# main.net
KiCad netlist of a schematic drawn in EAGLE
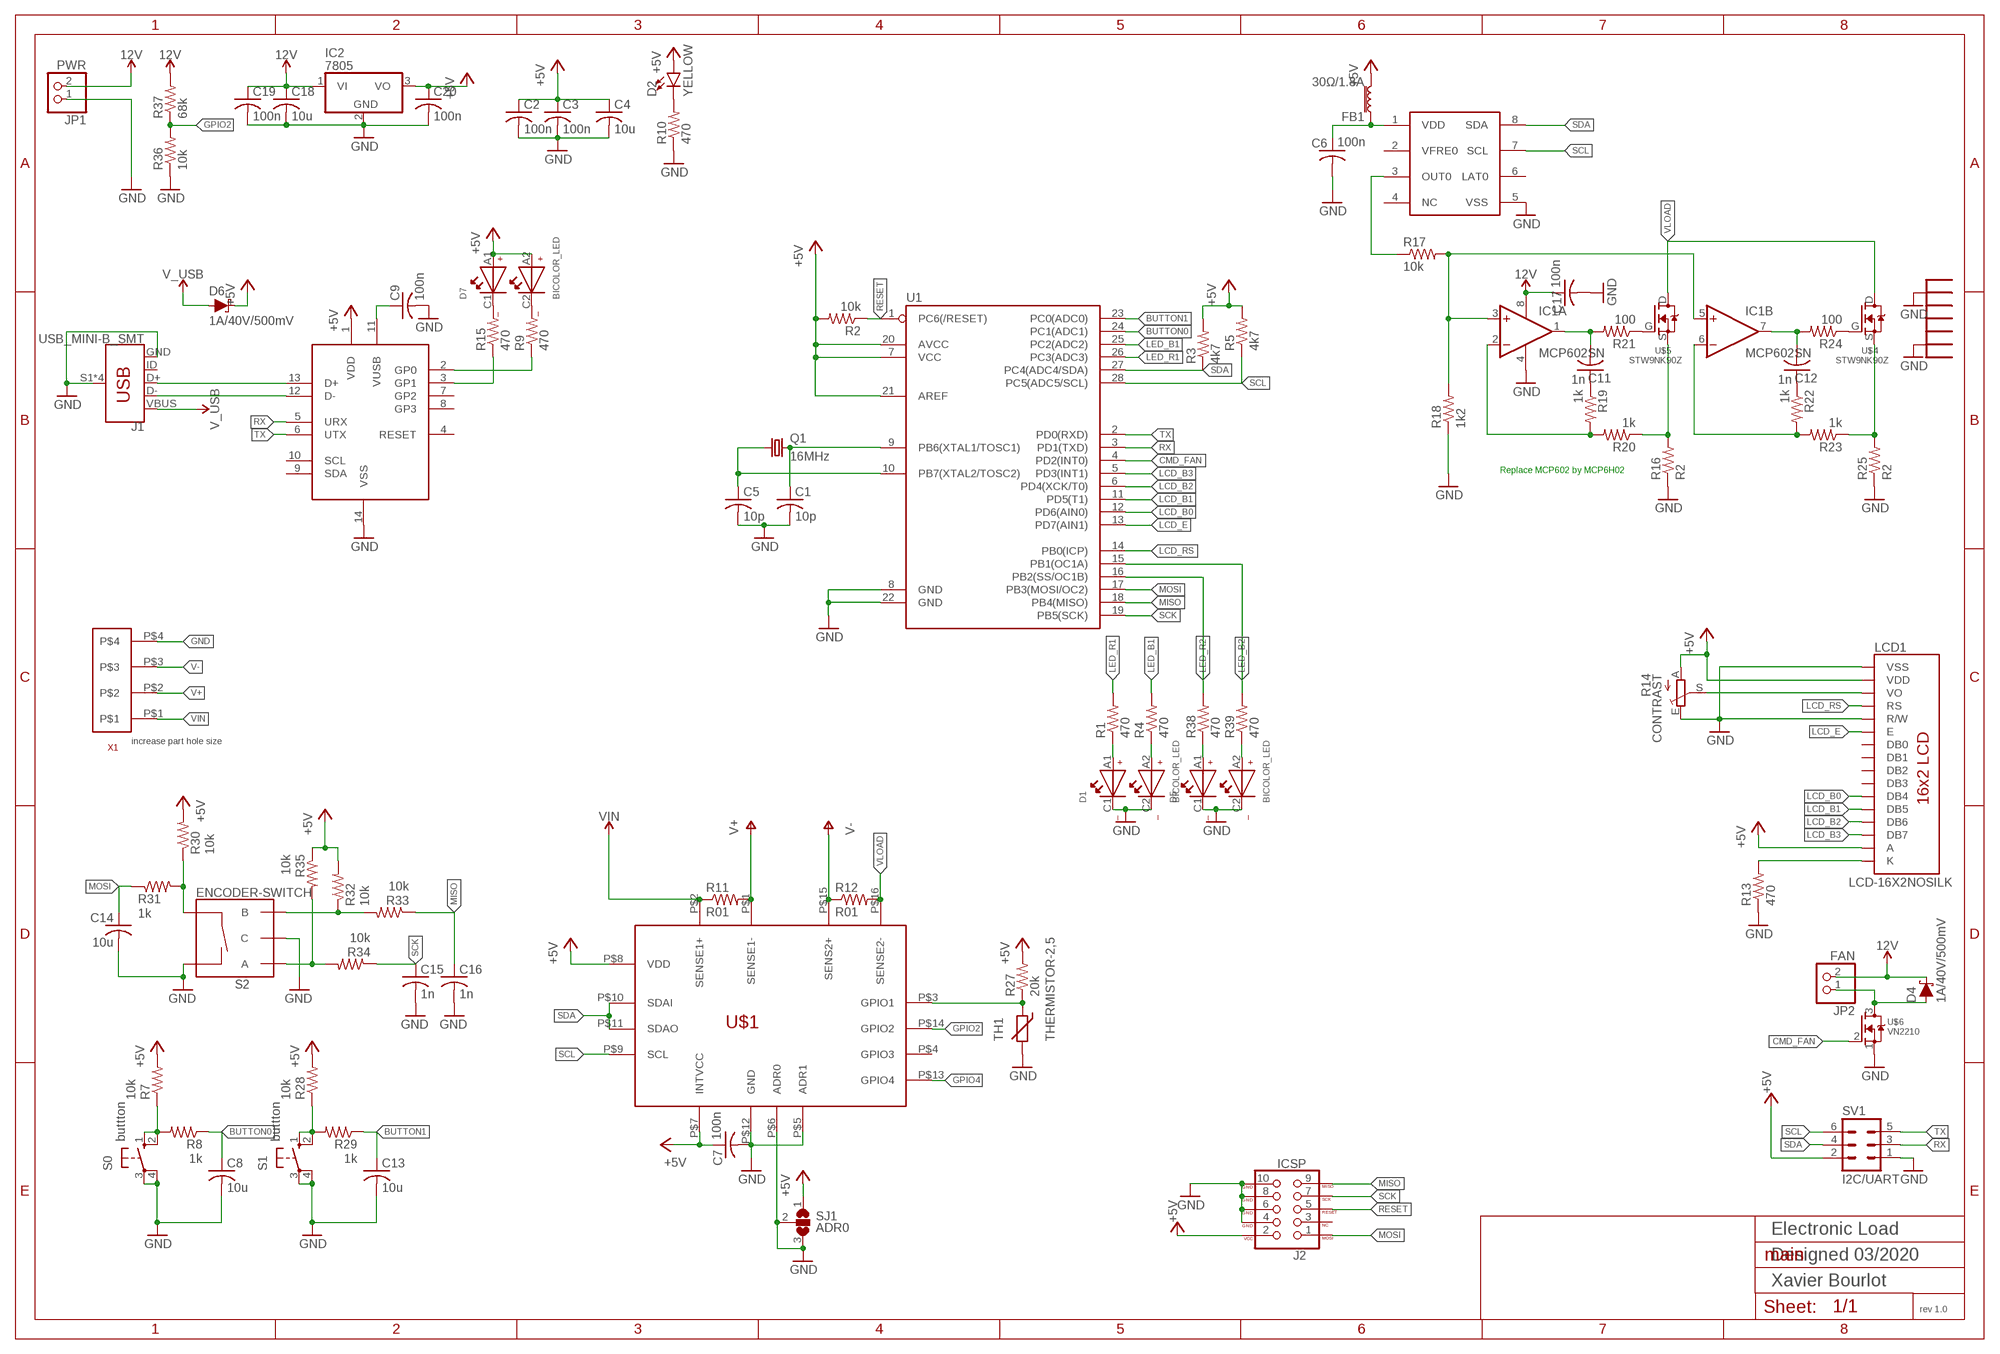
[diagram p0: schematic, sheet 1]

(export (version "E")
  (design (tool "Eeschema 10.0.6"))
  (components
    (comp (ref "BR1")
      (value "MCP2221A")
      (footprint "eagle-import:DIP14")
      (libsource (lib "eagle-import") (part "MCP2221A"))
    )
    (comp (ref "C1")
      (value "10p")
      (footprint "eagle-import:C0603")
      (libsource (lib "eagle-import") (part "C-USC0603"))
    )
    (comp (ref "C2")
      (value "100n")
      (footprint "eagle-import:C0603")
      (libsource (lib "eagle-import") (part "C-USC0603"))
    )
    (comp (ref "C3")
      (value "100n")
      (footprint "eagle-import:C0603")
      (libsource (lib "eagle-import") (part "C-USC0603"))
    )
    (comp (ref "C4")
      (value "10u")
      (footprint "eagle-import:C1206")
      (libsource (lib "eagle-import") (part "C-USC1206"))
    )
    (comp (ref "C5")
      (value "10p")
      (footprint "eagle-import:C0603")
      (libsource (lib "eagle-import") (part "C-USC0603"))
    )
    (comp (ref "C6")
      (value "100n")
      (footprint "eagle-import:C0603")
      (libsource (lib "eagle-import") (part "C-USC0603"))
    )
    (comp (ref "C7")
      (value "100n")
      (footprint "eagle-import:C0603")
      (libsource (lib "eagle-import") (part "C-USC0603"))
    )
    (comp (ref "C8")
      (value "10u")
      (footprint "eagle-import:C0603")
      (libsource (lib "eagle-import") (part "C-USC0603"))
    )
    (comp (ref "C9")
      (value "100n")
      (footprint "eagle-import:C0603")
      (libsource (lib "eagle-import") (part "C-USC0603"))
    )
    (comp (ref "C11")
      (value "1n")
      (footprint "eagle-import:C0805")
      (libsource (lib "eagle-import") (part "C-USC0805"))
    )
    (comp (ref "C12")
      (value "1n")
      (footprint "eagle-import:C0805")
      (libsource (lib "eagle-import") (part "C-USC0805"))
    )
    (comp (ref "C13")
      (value "10u")
      (footprint "eagle-import:C0603")
      (libsource (lib "eagle-import") (part "C-USC0603"))
    )
    (comp (ref "C14")
      (value "10u")
      (footprint "eagle-import:C0603")
      (libsource (lib "eagle-import") (part "C-USC0603"))
    )
    (comp (ref "C15")
      (value "1n")
      (footprint "eagle-import:C0603")
      (libsource (lib "eagle-import") (part "C-USC0603"))
    )
    (comp (ref "C16")
      (value "1n")
      (footprint "eagle-import:C0603")
      (libsource (lib "eagle-import") (part "C-USC0603"))
    )
    (comp (ref "C17")
      (value "100n")
      (footprint "eagle-import:C0603")
      (libsource (lib "eagle-import") (part "C-USC0603"))
    )
    (comp (ref "C18")
      (value "10u")
      (footprint "eagle-import:C1206")
      (libsource (lib "eagle-import") (part "C-USC1206"))
    )
    (comp (ref "C19")
      (value "100n")
      (footprint "eagle-import:C0603")
      (libsource (lib "eagle-import") (part "C-USC0603"))
    )
    (comp (ref "C20")
      (value "100n")
      (footprint "eagle-import:C0603")
      (libsource (lib "eagle-import") (part "C-USC0603"))
    )
    (comp (ref "D1")
      (value "BICOLOR_LED")
      (footprint "eagle-import:BICOLOR_LED")
      (libsource (lib "eagle-import") (part "BICOLOR_LED"))
    )
    (comp (ref "D2")
      (value "YELLOW")
      (footprint "eagle-import:LED_3MM")
      (libsource (lib "eagle-import") (part "LED3MM"))
    )
    (comp (ref "D4")
      (value "1A/40V/500mV")
      (footprint "eagle-import:SMA-DIODE")
      (libsource (lib "eagle-import") (part "DIODE-SCHOTTKY-SS14"))
    )
    (comp (ref "D5")
      (value "BICOLOR_LED")
      (footprint "eagle-import:BICOLOR_LED")
      (libsource (lib "eagle-import") (part "BICOLOR_LED"))
    )
    (comp (ref "D6")
      (value "1A/40V/500mV")
      (footprint "eagle-import:SMA-DIODE")
      (libsource (lib "eagle-import") (part "DIODE-SCHOTTKY-SS14"))
    )
    (comp (ref "D7")
      (value "BICOLOR_LED")
      (footprint "eagle-import:BICOLOR_LED")
      (libsource (lib "eagle-import") (part "BICOLOR_LED"))
    )
    (comp (ref "FB1")
      (value "30Ω/1.8A")
      (footprint "eagle-import:0603")
      (libsource (lib "eagle-import") (part "FERRITE_BEAD-0603"))
    )
    (comp (ref "IC1")
      (value "MCP602SN")
      (footprint "eagle-import:SO08")
      (libsource (lib "eagle-import") (part "MCP602SN"))
    )
    (comp (ref "IC2")
      (value "7805")
      (footprint "eagle-import:TO220V")
      (libsource (lib "eagle-import") (part "78TV6"))
    )
    (comp (ref "J1")
      (value "USB_MINI-B_SMT")
      (footprint "eagle-import:USB-MINIB")
      (libsource (lib "eagle-import") (part "USB_MINI-B_SMT"))
    )
    (comp (ref "J2")
      (value "ICSP")
      (footprint "eagle-import:2X5-SHROUDED")
      (libsource (lib "eagle-import") (part "AVR_SPI_PROG_5X2PTH2"))
    )
    (comp (ref "JP1")
      (value "PWR")
      (footprint "eagle-import:1X02")
      (libsource (lib "eagle-import") (part "PINHD-1X2"))
    )
    (comp (ref "JP2")
      (value "FAN")
      (footprint "eagle-import:1X02")
      (libsource (lib "eagle-import") (part "PINHD-1X2"))
    )
    (comp (ref "LCD1")
      (value "LCD-16X2NOSILK")
      (footprint "eagle-import:LCD-16X2_NOSILK")
      (libsource (lib "eagle-import") (part "LCD-16X2NOSILK"))
    )
    (comp (ref "Q1")
      (value "16MHz")
      (footprint "eagle-import:HC49U70")
      (libsource (lib "eagle-import") (part "CRYSTALHC49U70"))
    )
    (comp (ref "R1")
      (value "470")
      (footprint "eagle-import:R0805")
      (libsource (lib "eagle-import") (part "R-US_R0805"))
    )
    (comp (ref "R2")
      (value "10k")
      (footprint "eagle-import:R0805")
      (libsource (lib "eagle-import") (part "R-US_R0805"))
    )
    (comp (ref "R3")
      (value "4k7")
      (footprint "eagle-import:R0805")
      (libsource (lib "eagle-import") (part "R-US_R0805"))
    )
    (comp (ref "R4")
      (value "470")
      (footprint "eagle-import:R0805")
      (libsource (lib "eagle-import") (part "R-US_R0805"))
    )
    (comp (ref "R5")
      (value "4k7")
      (footprint "eagle-import:R0805")
      (libsource (lib "eagle-import") (part "R-US_R0805"))
    )
    (comp (ref "R7")
      (value "10k")
      (footprint "eagle-import:R0805")
      (libsource (lib "eagle-import") (part "R-US_R0805"))
    )
    (comp (ref "R8")
      (value "1k")
      (footprint "eagle-import:R0805")
      (libsource (lib "eagle-import") (part "R-US_R0805"))
    )
    (comp (ref "R9")
      (value "470")
      (footprint "eagle-import:R0805")
      (libsource (lib "eagle-import") (part "R-US_R0805"))
    )
    (comp (ref "R10")
      (value "470")
      (footprint "eagle-import:R0805")
      (libsource (lib "eagle-import") (part "R-US_R0805"))
    )
    (comp (ref "R11")
      (value "R01")
      (footprint "eagle-import:R2512")
      (libsource (lib "eagle-import") (part "R-US_R2512"))
    )
    (comp (ref "R12")
      (value "R01")
      (footprint "eagle-import:R2512")
      (libsource (lib "eagle-import") (part "R-US_R2512"))
    )
    (comp (ref "R13")
      (value "470")
      (footprint "eagle-import:R0805")
      (libsource (lib "eagle-import") (part "R-US_R0805"))
    )
    (comp (ref "R14")
      (value "CONTRAST")
      (footprint "eagle-import:RJ9W")
      (libsource (lib "eagle-import") (part "TRIM_EU-RJ9W"))
    )
    (comp (ref "R15")
      (value "470")
      (footprint "eagle-import:R0805")
      (libsource (lib "eagle-import") (part "R-US_R0805"))
    )
    (comp (ref "R16")
      (value "R2")
      (footprint "eagle-import:R2512")
      (libsource (lib "eagle-import") (part "R-US_R2512"))
    )
    (comp (ref "R17")
      (value "10k")
      (footprint "eagle-import:R0805")
      (libsource (lib "eagle-import") (part "R-US_R0805"))
    )
    (comp (ref "R18")
      (value "1k2")
      (footprint "eagle-import:R0805")
      (libsource (lib "eagle-import") (part "R-US_R0805"))
    )
    (comp (ref "R19")
      (value "1k")
      (footprint "eagle-import:R0805")
      (libsource (lib "eagle-import") (part "R-US_R0805"))
    )
    (comp (ref "R20")
      (value "1k")
      (footprint "eagle-import:R0805")
      (libsource (lib "eagle-import") (part "R-US_R0805"))
    )
    (comp (ref "R21")
      (value "100")
      (footprint "eagle-import:R0805")
      (libsource (lib "eagle-import") (part "R-US_R0805"))
    )
    (comp (ref "R22")
      (value "1k")
      (footprint "eagle-import:R0805")
      (libsource (lib "eagle-import") (part "R-US_R0805"))
    )
    (comp (ref "R23")
      (value "1k")
      (footprint "eagle-import:R0805")
      (libsource (lib "eagle-import") (part "R-US_R0805"))
    )
    (comp (ref "R24")
      (value "100")
      (footprint "eagle-import:R0805")
      (libsource (lib "eagle-import") (part "R-US_R0805"))
    )
    (comp (ref "R25")
      (value "R2")
      (footprint "eagle-import:R2512")
      (libsource (lib "eagle-import") (part "R-US_R2512"))
    )
    (comp (ref "R27")
      (value "20k")
      (footprint "eagle-import:R0805")
      (libsource (lib "eagle-import") (part "R-US_R0805"))
    )
    (comp (ref "R28")
      (value "10k")
      (footprint "eagle-import:R0805")
      (libsource (lib "eagle-import") (part "R-US_R0805"))
    )
    (comp (ref "R29")
      (value "1k")
      (footprint "eagle-import:R0805")
      (libsource (lib "eagle-import") (part "R-US_R0805"))
    )
    (comp (ref "R30")
      (value "10k")
      (footprint "eagle-import:R0805")
      (libsource (lib "eagle-import") (part "R-US_R0805"))
    )
    (comp (ref "R31")
      (value "1k")
      (footprint "eagle-import:R0805")
      (libsource (lib "eagle-import") (part "R-US_R0805"))
    )
    (comp (ref "R32")
      (value "10k")
      (footprint "eagle-import:R0805")
      (libsource (lib "eagle-import") (part "R-US_R0805"))
    )
    (comp (ref "R33")
      (value "10k")
      (footprint "eagle-import:R0805")
      (libsource (lib "eagle-import") (part "R-US_R0805"))
    )
    (comp (ref "R34")
      (value "10k")
      (footprint "eagle-import:R0805")
      (libsource (lib "eagle-import") (part "R-US_R0805"))
    )
    (comp (ref "R35")
      (value "10k")
      (footprint "eagle-import:R0805")
      (libsource (lib "eagle-import") (part "R-US_R0805"))
    )
    (comp (ref "R36")
      (value "10k")
      (footprint "eagle-import:R0805")
      (libsource (lib "eagle-import") (part "R-US_R0805"))
    )
    (comp (ref "R37")
      (value "68k")
      (footprint "eagle-import:R0805")
      (libsource (lib "eagle-import") (part "R-US_R0805"))
    )
    (comp (ref "R38")
      (value "470")
      (footprint "eagle-import:R0805")
      (libsource (lib "eagle-import") (part "R-US_R0805"))
    )
    (comp (ref "R39")
      (value "470")
      (footprint "eagle-import:R0805")
      (libsource (lib "eagle-import") (part "R-US_R0805"))
    )
    (comp (ref "S0")
      (value "buttton")
      (footprint "eagle-import:B3F-10XX")
      (fields (field (name "MPN") "B3F-1000"))
      (libsource (lib "eagle-import") (part "10-XX"))
    )
    (comp (ref "S1")
      (value "buttton")
      (footprint "eagle-import:B3F-10XX")
      (fields (field (name "MPN") "B3F-1000"))
      (libsource (lib "eagle-import") (part "10-XX"))
    )
    (comp (ref "S2")
      (value "ENCODER-SWITCH")
      (footprint "eagle-import:ROTARY_ENC_PLAIN")
      (libsource (lib "eagle-import") (part "ENCODER-SWITCH"))
    )
    (comp (ref "SJ1")
      (value "ADR0")
      (footprint "eagle-import:SJ_2")
      (libsource (lib "eagle-import") (part "SJ2W"))
    )
    (comp (ref "SV1")
      (value "I2C/UART")
      (footprint "eagle-import:MA03-2")
      (libsource (lib "eagle-import") (part "MA03-2"))
    )
    (comp (ref "TH1")
      (value "THERMISTOR-2,5")
      (footprint "eagle-import:RS-2,5")
      (libsource (lib "eagle-import") (part "THERMISTOR-2,5"))
    )
    (comp (ref "U$1")
      (value "LTC2992")
      (footprint "eagle-import:MSOP16")
      (libsource (lib "eagle-import") (part "LTC2992"))
    )
    (comp (ref "U$2")
      (value "HEATSINK_0NOSILK")
      (footprint "eagle-import:HEATSINK_01")
      (libsource (lib "eagle-import") (part "HEATSINK_0NOSILK"))
    )
    (comp (ref "U$3")
      (value "MCP47FEB21")
      (footprint "eagle-import:TSSOP8")
      (libsource (lib "eagle-import") (part "MCP47FEB21"))
    )
    (comp (ref "U$4")
      (value "STW9NK90Z")
      (footprint "eagle-import:TO247BV")
      (libsource (lib "eagle-import") (part "STW9NK90Z"))
    )
    (comp (ref "U$5")
      (value "STW9NK90Z")
      (footprint "eagle-import:TO247BV")
      (libsource (lib "eagle-import") (part "STW9NK90Z"))
    )
    (comp (ref "U$6")
      (value "VN2210")
      (footprint "eagle-import:TO92")
      (libsource (lib "eagle-import") (part "VN2210"))
    )
    (comp (ref "U1")
      (value "328P")
      (footprint "eagle-import:DIP28")
      (libsource (lib "eagle-import") (part "ATMEGA328P_PDIP"))
    )
    (comp (ref "X1")
      (value "SCREWTERM_5MM_4WAY")
      (footprint "eagle-import:SCREWTERM_5MM_4WAY")
      (libsource (lib "eagle-import") (part "SCREWTERM_5MM_4WAY"))
    )
  )
  (nets
    (net (code "1") (name "+5V") (class "Default")
      (node (ref "BR1") (pin "1") (pinfunction "VDD_1") (pintype "bidirectional"))
      (node (ref "C2") (pin "1") (pinfunction "1_1") (pintype "passive"))
      (node (ref "C20") (pin "1") (pinfunction "1_1") (pintype "passive"))
      (node (ref "C3") (pin "1") (pinfunction "1_1") (pintype "passive"))
      (node (ref "C4") (pin "1") (pinfunction "1_1") (pintype "passive"))
      (node (ref "C7") (pin "1") (pinfunction "1_1") (pintype "passive"))
      (node (ref "D2") (pin "A") (pinfunction "A_A") (pintype "passive"))
      (node (ref "D6") (pin "C") (pinfunction "C_C") (pintype "passive"))
      (node (ref "D7") (pin "A1") (pinfunction "A1_A1") (pintype "passive"))
      (node (ref "D7") (pin "A2") (pinfunction "A2_A2") (pintype "passive"))
      (node (ref "FB1") (pin "2") (pinfunction "2_2") (pintype "passive"))
      (node (ref "IC2") (pin "3") (pinfunction "VO_3") (pintype "passive"))
      (node (ref "J2") (pin "2") (pinfunction "VCC_2") (pintype "power_in"))
      (node (ref "LCD1") (pin "15") (pinfunction "A_15") (pintype "power_in"))
      (node (ref "LCD1") (pin "2") (pinfunction "VDD_2") (pintype "power_in"))
      (node (ref "R14") (pin "A") (pinfunction "A_A") (pintype "passive"))
      (node (ref "R2") (pin "2") (pinfunction "2_2") (pintype "passive"))
      (node (ref "R27") (pin "2") (pinfunction "2_2") (pintype "passive"))
      (node (ref "R28") (pin "2") (pinfunction "2_2") (pintype "passive"))
      (node (ref "R3") (pin "2") (pinfunction "2_2") (pintype "passive"))
      (node (ref "R30") (pin "2") (pinfunction "2_2") (pintype "passive"))
      (node (ref "R32") (pin "2") (pinfunction "2_2") (pintype "passive"))
      (node (ref "R35") (pin "1") (pinfunction "1_1") (pintype "passive"))
      (node (ref "R5") (pin "2") (pinfunction "2_2") (pintype "passive"))
      (node (ref "R7") (pin "2") (pinfunction "2_2") (pintype "passive"))
      (node (ref "SJ1") (pin "1") (pinfunction "1_1") (pintype "passive"))
      (node (ref "SV1") (pin "2") (pinfunction "2_2") (pintype "passive"))
      (node (ref "U$1") (pin "P$7") (pinfunction "INTVCC_P$7") (pintype "bidirectional"))
      (node (ref "U$1") (pin "P$8") (pinfunction "VDD_P$8") (pintype "bidirectional"))
      (node (ref "U1") (pin "20") (pinfunction "AVCC_20") (pintype "bidirectional"))
      (node (ref "U1") (pin "21") (pinfunction "AREF_21") (pintype "bidirectional"))
      (node (ref "U1") (pin "7") (pinfunction "VCC_7") (pintype "bidirectional"))
    )
    (net (code "2") (name "12V") (class "Default")
      (node (ref "C17") (pin "1") (pinfunction "1_1") (pintype "passive"))
      (node (ref "C18") (pin "1") (pinfunction "1_1") (pintype "passive"))
      (node (ref "C19") (pin "1") (pinfunction "1_1") (pintype "passive"))
      (node (ref "D4") (pin "C") (pinfunction "C_C") (pintype "passive"))
      (node (ref "IC1") (pin "8") (pinfunction "V+_8") (pintype "power_in"))
      (node (ref "IC2") (pin "1") (pinfunction "VI_1") (pintype "input"))
      (node (ref "JP1") (pin "2") (pinfunction "2_2") (pintype "passive"))
      (node (ref "JP2") (pin "2") (pinfunction "2_2") (pintype "passive"))
      (node (ref "R37") (pin "2") (pinfunction "2_2") (pintype "passive"))
    )
    (net (code "3") (name "BUTTON0") (class "Default")
      (node (ref "C8") (pin "1") (pinfunction "1_1") (pintype "passive"))
      (node (ref "R8") (pin "1") (pinfunction "1_1") (pintype "passive"))
      (node (ref "U1") (pin "24") (pinfunction "PC1(ADC1)_24") (pintype "bidirectional"))
    )
    (net (code "4") (name "BUTTON1") (class "Default")
      (node (ref "C13") (pin "1") (pinfunction "1_1") (pintype "passive"))
      (node (ref "R29") (pin "1") (pinfunction "1_1") (pintype "passive"))
      (node (ref "U1") (pin "23") (pinfunction "PC0(ADC0)_23") (pintype "bidirectional"))
    )
    (net (code "5") (name "CMD_FAN") (class "Default")
      (node (ref "U$6") (pin "2") (pinfunction "G_2") (pintype "bidirectional"))
      (node (ref "U1") (pin "4") (pinfunction "PD2(INT0)_4") (pintype "bidirectional"))
    )
    (net (code "6") (name "GND") (class "Default")
      (node (ref "BR1") (pin "14") (pinfunction "VSS_14") (pintype "bidirectional"))
      (node (ref "C1") (pin "2") (pinfunction "2_2") (pintype "passive"))
      (node (ref "C13") (pin "2") (pinfunction "2_2") (pintype "passive"))
      (node (ref "C14") (pin "2") (pinfunction "2_2") (pintype "passive"))
      (node (ref "C15") (pin "2") (pinfunction "2_2") (pintype "passive"))
      (node (ref "C16") (pin "2") (pinfunction "2_2") (pintype "passive"))
      (node (ref "C17") (pin "2") (pinfunction "2_2") (pintype "passive"))
      (node (ref "C18") (pin "2") (pinfunction "2_2") (pintype "passive"))
      (node (ref "C19") (pin "2") (pinfunction "2_2") (pintype "passive"))
      (node (ref "C2") (pin "2") (pinfunction "2_2") (pintype "passive"))
      (node (ref "C20") (pin "2") (pinfunction "2_2") (pintype "passive"))
      (node (ref "C3") (pin "2") (pinfunction "2_2") (pintype "passive"))
      (node (ref "C4") (pin "2") (pinfunction "2_2") (pintype "passive"))
      (node (ref "C5") (pin "2") (pinfunction "2_2") (pintype "passive"))
      (node (ref "C6") (pin "2") (pinfunction "2_2") (pintype "passive"))
      (node (ref "C7") (pin "2") (pinfunction "2_2") (pintype "passive"))
      (node (ref "C8") (pin "2") (pinfunction "2_2") (pintype "passive"))
      (node (ref "C9") (pin "2") (pinfunction "2_2") (pintype "passive"))
      (node (ref "D1") (pin "C1") (pinfunction "C1_C1") (pintype "passive"))
      (node (ref "D1") (pin "C2") (pinfunction "C2_C2") (pintype "passive"))
      (node (ref "D5") (pin "C1") (pinfunction "C1_C1") (pintype "passive"))
      (node (ref "D5") (pin "C2") (pinfunction "C2_C2") (pintype "passive"))
      (node (ref "IC1") (pin "4") (pinfunction "V-_4") (pintype "power_in"))
      (node (ref "IC2") (pin "2") (pinfunction "GND_2") (pintype "passive"))
      (node (ref "J1") (pin "GND") (pinfunction "GND_GND") (pintype "power_in"))
      (node (ref "J1") (pin "S1") (pinfunction "SHIELD_S1") (pintype "bidirectional"))
      (node (ref "J1") (pin "S2") (pinfunction "SHIELD_S2") (pintype "bidirectional"))
      (node (ref "J1") (pin "S3") (pinfunction "SHIELD_S3") (pintype "bidirectional"))
      (node (ref "J1") (pin "S4") (pinfunction "SHIELD_S4") (pintype "bidirectional"))
      (node (ref "J2") (pin "10") (pinfunction "GND_10") (pintype "power_in"))
      (node (ref "J2") (pin "4") (pinfunction "GND_4") (pintype "power_in"))
      (node (ref "J2") (pin "6") (pinfunction "GND_6") (pintype "power_in"))
      (node (ref "J2") (pin "8") (pinfunction "GND_8") (pintype "power_in"))
      (node (ref "JP1") (pin "1") (pinfunction "1_1") (pintype "passive"))
      (node (ref "LCD1") (pin "1") (pinfunction "VSS_1") (pintype "power_in"))
      (node (ref "LCD1") (pin "5") (pinfunction "R/W_5") (pintype "input"))
      (node (ref "R10") (pin "1") (pinfunction "1_1") (pintype "passive"))
      (node (ref "R13") (pin "1") (pinfunction "1_1") (pintype "passive"))
      (node (ref "R14") (pin "E") (pinfunction "E_E") (pintype "passive"))
      (node (ref "R16") (pin "1") (pinfunction "1_1") (pintype "passive"))
      (node (ref "R18") (pin "1") (pinfunction "1_1") (pintype "passive"))
      (node (ref "R25") (pin "1") (pinfunction "1_1") (pintype "passive"))
      (node (ref "R36") (pin "1") (pinfunction "1_1") (pintype "passive"))
      (node (ref "S0") (pin "3") (pinfunction "P_3") (pintype "passive"))
      (node (ref "S0") (pin "4") (pinfunction "P1_4") (pintype "passive"))
      (node (ref "S1") (pin "3") (pinfunction "P_3") (pintype "passive"))
      (node (ref "S1") (pin "4") (pinfunction "P1_4") (pintype "passive"))
      (node (ref "S2") (pin "C") (pinfunction "C_C") (pintype "bidirectional"))
      (node (ref "S2") (pin "SW-") (pinfunction "SW-_SW-") (pintype "bidirectional"))
      (node (ref "SJ1") (pin "2") (pinfunction "2_2") (pintype "passive"))
      (node (ref "SJ1") (pin "3") (pinfunction "3_3") (pintype "passive"))
      (node (ref "SV1") (pin "1") (pinfunction "1_1") (pintype "passive"))
      (node (ref "TH1") (pin "2") (pinfunction "2_2") (pintype "passive"))
      (node (ref "U$1") (pin "P$12") (pinfunction "GND_P$12") (pintype "bidirectional"))
      (node (ref "U$1") (pin "P$5") (pinfunction "ADR1_P$5") (pintype "bidirectional"))
      (node (ref "U$1") (pin "P$6") (pinfunction "ADR0_P$6") (pintype "bidirectional"))
      (node (ref "U$2") (pin "P$1") (pinfunction "P$1_P$1") (pintype "bidirectional"))
      (node (ref "U$2") (pin "P$2") (pinfunction "P$2_P$2") (pintype "bidirectional"))
      (node (ref "U$3") (pin "5") (pinfunction "VSS_5") (pintype "bidirectional"))
      (node (ref "U$6") (pin "1") (pinfunction "S_1") (pintype "bidirectional"))
      (node (ref "U1") (pin "22") (pinfunction "GND_22") (pintype "bidirectional"))
      (node (ref "U1") (pin "8") (pinfunction "GND_8") (pintype "bidirectional"))
      (node (ref "X1") (pin "P$4") (pinfunction "P$4_P$4") (pintype "bidirectional"))
    )
    (net (code "7") (name "GPIO2") (class "Default")
      (node (ref "R36") (pin "2") (pinfunction "2_2") (pintype "passive"))
      (node (ref "R37") (pin "1") (pinfunction "1_1") (pintype "passive"))
      (node (ref "U$1") (pin "P$14") (pinfunction "GPIO2_P$14") (pintype "bidirectional"))
    )
    (net (code "8") (name "GPIO4") (class "Default")
      (node (ref "U$1") (pin "P$13") (pinfunction "GPIO4_P$13") (pintype "bidirectional"))
    )
    (net (code "9") (name "LCD_B0") (class "Default")
      (node (ref "LCD1") (pin "11") (pinfunction "DB4_11") (pintype "bidirectional"))
      (node (ref "U1") (pin "12") (pinfunction "PD6(AIN0)_12") (pintype "bidirectional"))
    )
    (net (code "10") (name "LCD_B1") (class "Default")
      (node (ref "LCD1") (pin "12") (pinfunction "DB5_12") (pintype "bidirectional"))
      (node (ref "U1") (pin "11") (pinfunction "PD5(T1)_11") (pintype "bidirectional"))
    )
    (net (code "11") (name "LCD_B2") (class "Default")
      (node (ref "LCD1") (pin "13") (pinfunction "DB6_13") (pintype "bidirectional"))
      (node (ref "U1") (pin "6") (pinfunction "PD4(XCK/T0)_6") (pintype "bidirectional"))
    )
    (net (code "12") (name "LCD_B3") (class "Default")
      (node (ref "LCD1") (pin "14") (pinfunction "DB7_14") (pintype "bidirectional"))
      (node (ref "U1") (pin "5") (pinfunction "PD3(INT1)_5") (pintype "bidirectional"))
    )
    (net (code "13") (name "LCD_E") (class "Default")
      (node (ref "LCD1") (pin "6") (pinfunction "E_6") (pintype "input"))
      (node (ref "U1") (pin "13") (pinfunction "PD7(AIN1)_13") (pintype "bidirectional"))
    )
    (net (code "14") (name "LCD_RS") (class "Default")
      (node (ref "LCD1") (pin "4") (pinfunction "RS_4") (pintype "input"))
      (node (ref "U1") (pin "14") (pinfunction "PB0(ICP)_14") (pintype "bidirectional"))
    )
    (net (code "15") (name "LED_B1") (class "Default")
      (node (ref "R4") (pin "2") (pinfunction "2_2") (pintype "passive"))
      (node (ref "U1") (pin "25") (pinfunction "PC2(ADC2)_25") (pintype "bidirectional"))
    )
    (net (code "16") (name "LED_B2") (class "Default")
      (node (ref "R39") (pin "2") (pinfunction "2_2") (pintype "passive"))
      (node (ref "U1") (pin "15") (pinfunction "PB1(OC1A)_15") (pintype "bidirectional"))
    )
    (net (code "17") (name "LED_R1") (class "Default")
      (node (ref "R1") (pin "2") (pinfunction "2_2") (pintype "passive"))
      (node (ref "U1") (pin "26") (pinfunction "PC3(ADC3)_26") (pintype "bidirectional"))
    )
    (net (code "18") (name "LED_R2") (class "Default")
      (node (ref "R38") (pin "2") (pinfunction "2_2") (pintype "passive"))
      (node (ref "U1") (pin "16") (pinfunction "PB2(SS/OC1B)_16") (pintype "bidirectional"))
    )
    (net (code "19") (name "MISO") (class "Default")
      (node (ref "C16") (pin "1") (pinfunction "1_1") (pintype "passive"))
      (node (ref "J2") (pin "9") (pinfunction "MISO_9") (pintype "passive"))
      (node (ref "R33") (pin "1") (pinfunction "1_1") (pintype "passive"))
      (node (ref "U1") (pin "18") (pinfunction "PB4(MISO)_18") (pintype "bidirectional"))
    )
    (net (code "20") (name "MOSI") (class "Default")
      (node (ref "C14") (pin "1") (pinfunction "1_1") (pintype "passive"))
      (node (ref "J2") (pin "1") (pinfunction "MOSI_1") (pintype "passive"))
      (node (ref "R31") (pin "1") (pinfunction "1_1") (pintype "passive"))
      (node (ref "U1") (pin "17") (pinfunction "PB3(MOSI/OC2)_17") (pintype "bidirectional"))
    )
    (net (code "21") (name "Net-(BR1-D+)") (class "Default")
      (node (ref "BR1") (pin "13") (pinfunction "D+_13") (pintype "bidirectional"))
      (node (ref "J1") (pin "D+") (pinfunction "D+_D+") (pintype "bidirectional"))
    )
    (net (code "22") (name "Net-(BR1-D-)") (class "Default")
      (node (ref "BR1") (pin "12") (pinfunction "D-_12") (pintype "bidirectional"))
      (node (ref "J1") (pin "D-") (pinfunction "D-_D-") (pintype "bidirectional"))
    )
    (net (code "23") (name "Net-(BR1-GP0)") (class "Default")
      (node (ref "BR1") (pin "2") (pinfunction "GP0_2") (pintype "bidirectional"))
      (node (ref "R9") (pin "1") (pinfunction "1_1") (pintype "passive"))
    )
    (net (code "24") (name "Net-(BR1-GP1)") (class "Default")
      (node (ref "BR1") (pin "3") (pinfunction "GP1_3") (pintype "bidirectional"))
      (node (ref "R15") (pin "1") (pinfunction "1_1") (pintype "passive"))
    )
    (net (code "25") (name "Net-(BR1-VUSB)") (class "Default")
      (node (ref "BR1") (pin "11") (pinfunction "VUSB_11") (pintype "bidirectional"))
      (node (ref "C9") (pin "1") (pinfunction "1_1") (pintype "passive"))
    )
    (net (code "26") (name "Net-(C11-Pad1)") (class "Default")
      (node (ref "C11") (pin "1") (pinfunction "1_1") (pintype "passive"))
      (node (ref "R19") (pin "1") (pinfunction "1_1") (pintype "passive"))
    )
    (net (code "27") (name "Net-(C12-Pad1)") (class "Default")
      (node (ref "C12") (pin "1") (pinfunction "1_1") (pintype "passive"))
      (node (ref "R22") (pin "1") (pinfunction "1_1") (pintype "passive"))
    )
    (net (code "28") (name "Net-(D1-PadA1)") (class "Default")
      (node (ref "D1") (pin "A1") (pinfunction "A1_A1") (pintype "passive"))
      (node (ref "R1") (pin "1") (pinfunction "1_1") (pintype "passive"))
    )
    (net (code "29") (name "Net-(D1-PadA2)") (class "Default")
      (node (ref "D1") (pin "A2") (pinfunction "A2_A2") (pintype "passive"))
      (node (ref "R4") (pin "1") (pinfunction "1_1") (pintype "passive"))
    )
    (net (code "30") (name "Net-(D2-C)") (class "Default")
      (node (ref "D2") (pin "K") (pinfunction "C_K") (pintype "passive"))
      (node (ref "R10") (pin "2") (pinfunction "2_2") (pintype "passive"))
    )
    (net (code "31") (name "Net-(D5-PadA1)") (class "Default")
      (node (ref "D5") (pin "A1") (pinfunction "A1_A1") (pintype "passive"))
      (node (ref "R38") (pin "1") (pinfunction "1_1") (pintype "passive"))
    )
    (net (code "32") (name "Net-(D5-PadA2)") (class "Default")
      (node (ref "D5") (pin "A2") (pinfunction "A2_A2") (pintype "passive"))
      (node (ref "R39") (pin "1") (pinfunction "1_1") (pintype "passive"))
    )
    (net (code "33") (name "Net-(D7-PadC1)") (class "Default")
      (node (ref "D7") (pin "C1") (pinfunction "C1_C1") (pintype "passive"))
      (node (ref "R15") (pin "2") (pinfunction "2_2") (pintype "passive"))
    )
    (net (code "34") (name "Net-(D7-PadC2)") (class "Default")
      (node (ref "D7") (pin "C2") (pinfunction "C2_C2") (pintype "passive"))
      (node (ref "R9") (pin "2") (pinfunction "2_2") (pintype "passive"))
    )
    (net (code "35") (name "Net-(IC1A-+IN)") (class "Default")
      (node (ref "IC1") (pin "3") (pinfunction "+IN_3") (pintype "input"))
      (node (ref "IC1") (pin "5") (pinfunction "+IN_5") (pintype "input"))
      (node (ref "R17") (pin "2") (pinfunction "2_2") (pintype "passive"))
      (node (ref "R18") (pin "2") (pinfunction "2_2") (pintype "passive"))
    )
    (net (code "36") (name "Net-(IC1A--IN)") (class "Default")
      (node (ref "IC1") (pin "2") (pinfunction "-IN_2") (pintype "input"))
      (node (ref "R19") (pin "2") (pinfunction "2_2") (pintype "passive"))
      (node (ref "R20") (pin "2") (pinfunction "2_2") (pintype "passive"))
    )
    (net (code "37") (name "Net-(IC1A-OUT)") (class "Default")
      (node (ref "C11") (pin "2") (pinfunction "2_2") (pintype "passive"))
      (node (ref "IC1") (pin "1") (pinfunction "OUT_1") (pintype "output"))
      (node (ref "R21") (pin "2") (pinfunction "2_2") (pintype "passive"))
    )
    (net (code "38") (name "Net-(IC1B--IN)") (class "Default")
      (node (ref "IC1") (pin "6") (pinfunction "-IN_6") (pintype "input"))
      (node (ref "R22") (pin "2") (pinfunction "2_2") (pintype "passive"))
      (node (ref "R23") (pin "2") (pinfunction "2_2") (pintype "passive"))
    )
    (net (code "39") (name "Net-(IC1B-OUT)") (class "Default")
      (node (ref "C12") (pin "2") (pinfunction "2_2") (pintype "passive"))
      (node (ref "IC1") (pin "7") (pinfunction "OUT_7") (pintype "output"))
      (node (ref "R24") (pin "2") (pinfunction "2_2") (pintype "passive"))
    )
    (net (code "40") (name "Net-(LCD1-K)") (class "Default")
      (node (ref "LCD1") (pin "16") (pinfunction "K_16") (pintype "power_in"))
      (node (ref "R13") (pin "2") (pinfunction "2_2") (pintype "passive"))
    )
    (net (code "41") (name "Net-(LCD1-VO)") (class "Default")
      (node (ref "LCD1") (pin "3") (pinfunction "VO_3") (pintype "bidirectional"))
      (node (ref "R14") (pin "S") (pinfunction "S_S") (pintype "passive"))
    )
    (net (code "42") (name "Net-(R16-Pad2)") (class "Default")
      (node (ref "R16") (pin "2") (pinfunction "2_2") (pintype "passive"))
      (node (ref "R20") (pin "1") (pinfunction "1_1") (pintype "passive"))
      (node (ref "U$5") (pin "S") (pinfunction "S_S") (pintype "bidirectional"))
    )
    (net (code "43") (name "Net-(R21-Pad1)") (class "Default")
      (node (ref "R21") (pin "1") (pinfunction "1_1") (pintype "passive"))
      (node (ref "U$5") (pin "G") (pinfunction "G_G") (pintype "bidirectional"))
    )
    (net (code "44") (name "Net-(R23-Pad1)") (class "Default")
      (node (ref "R23") (pin "1") (pinfunction "1_1") (pintype "passive"))
      (node (ref "R25") (pin "2") (pinfunction "2_2") (pintype "passive"))
      (node (ref "U$4") (pin "S") (pinfunction "S_S") (pintype "bidirectional"))
    )
    (net (code "45") (name "Net-(R24-Pad1)") (class "Default")
      (node (ref "R24") (pin "1") (pinfunction "1_1") (pintype "passive"))
      (node (ref "U$4") (pin "G") (pinfunction "G_G") (pintype "bidirectional"))
    )
    (net (code "46") (name "Net-(R30-Pad1)") (class "Default")
      (node (ref "R30") (pin "1") (pinfunction "1_1") (pintype "passive"))
      (node (ref "R31") (pin "2") (pinfunction "2_2") (pintype "passive"))
      (node (ref "S2") (pin "SW+") (pinfunction "SW+_SW+") (pintype "bidirectional"))
    )
    (net (code "47") (name "Net-(R32-Pad1)") (class "Default")
      (node (ref "R32") (pin "1") (pinfunction "1_1") (pintype "passive"))
      (node (ref "R33") (pin "2") (pinfunction "2_2") (pintype "passive"))
      (node (ref "S2") (pin "B") (pinfunction "B_B") (pintype "bidirectional"))
    )
    (net (code "48") (name "Net-(R34-Pad2)") (class "Default")
      (node (ref "R34") (pin "2") (pinfunction "2_2") (pintype "passive"))
      (node (ref "R35") (pin "2") (pinfunction "2_2") (pintype "passive"))
      (node (ref "S2") (pin "A") (pinfunction "A_A") (pintype "bidirectional"))
    )
    (net (code "49") (name "Net-(S0-S)") (class "Default")
      (node (ref "R7") (pin "1") (pinfunction "1_1") (pintype "passive"))
      (node (ref "R8") (pin "2") (pinfunction "2_2") (pintype "passive"))
      (node (ref "S0") (pin "1") (pinfunction "S_1") (pintype "passive"))
      (node (ref "S0") (pin "2") (pinfunction "S1_2") (pintype "passive"))
    )
    (net (code "50") (name "Net-(S1-S)") (class "Default")
      (node (ref "R28") (pin "1") (pinfunction "1_1") (pintype "passive"))
      (node (ref "R29") (pin "2") (pinfunction "2_2") (pintype "passive"))
      (node (ref "S1") (pin "1") (pinfunction "S_1") (pintype "passive"))
      (node (ref "S1") (pin "2") (pinfunction "S1_2") (pintype "passive"))
    )
    (net (code "51") (name "Net-(U$1-GPIO1)") (class "Default")
      (node (ref "R27") (pin "1") (pinfunction "1_1") (pintype "passive"))
      (node (ref "TH1") (pin "1") (pinfunction "1_1") (pintype "passive"))
      (node (ref "U$1") (pin "P$3") (pinfunction "GPIO1_P$3") (pintype "bidirectional"))
    )
    (net (code "52") (name "Net-(U$3-OUT0)") (class "Default")
      (node (ref "R17") (pin "1") (pinfunction "1_1") (pintype "passive"))
      (node (ref "U$3") (pin "3") (pinfunction "OUT0_3") (pintype "bidirectional"))
    )
    (net (code "53") (name "Net-(U$3-VDD)") (class "Default")
      (node (ref "C6") (pin "1") (pinfunction "1_1") (pintype "passive"))
      (node (ref "FB1") (pin "1") (pinfunction "1_1") (pintype "passive"))
      (node (ref "U$3") (pin "1") (pinfunction "VDD_1") (pintype "bidirectional"))
    )
    (net (code "54") (name "Net-(U$6-D)") (class "Default")
      (node (ref "D4") (pin "A") (pinfunction "A_A") (pintype "passive"))
      (node (ref "JP2") (pin "1") (pinfunction "1_1") (pintype "passive"))
      (node (ref "U$6") (pin "3") (pinfunction "D_3") (pintype "bidirectional"))
    )
    (net (code "55") (name "Net-(U1-PB6(XTAL1{slash}TOSC1))") (class "Default")
      (node (ref "C1") (pin "1") (pinfunction "1_1") (pintype "passive"))
      (node (ref "Q1") (pin "2") (pinfunction "2_2") (pintype "passive"))
      (node (ref "U1") (pin "9") (pinfunction "PB6(XTAL1/TOSC1)_9") (pintype "bidirectional"))
    )
    (net (code "56") (name "Net-(U1-PB7(XTAL2{slash}TOSC2))") (class "Default")
      (node (ref "C5") (pin "1") (pinfunction "1_1") (pintype "passive"))
      (node (ref "Q1") (pin "1") (pinfunction "1_1") (pintype "passive"))
      (node (ref "U1") (pin "10") (pinfunction "PB7(XTAL2/TOSC2)_10") (pintype "bidirectional"))
    )
    (net (code "57") (name "RESET") (class "Default")
      (node (ref "J2") (pin "5") (pinfunction "RESET_5") (pintype "passive"))
      (node (ref "R2") (pin "1") (pinfunction "1_1") (pintype "passive"))
      (node (ref "U1") (pin "1") (pinfunction "PC6(/RESET)_1") (pintype "bidirectional"))
    )
    (net (code "58") (name "RX") (class "Default")
      (node (ref "BR1") (pin "5") (pinfunction "URX_5") (pintype "bidirectional"))
      (node (ref "SV1") (pin "3") (pinfunction "3_3") (pintype "passive"))
      (node (ref "U1") (pin "3") (pinfunction "PD1(TXD)_3") (pintype "bidirectional"))
    )
    (net (code "59") (name "SCK") (class "Default")
      (node (ref "C15") (pin "1") (pinfunction "1_1") (pintype "passive"))
      (node (ref "J2") (pin "7") (pinfunction "SCK_7") (pintype "passive"))
      (node (ref "R34") (pin "1") (pinfunction "1_1") (pintype "passive"))
      (node (ref "U1") (pin "19") (pinfunction "PB5(SCK)_19") (pintype "bidirectional"))
    )
    (net (code "60") (name "SCL") (class "Default")
      (node (ref "R5") (pin "1") (pinfunction "1_1") (pintype "passive"))
      (node (ref "SV1") (pin "6") (pinfunction "6_6") (pintype "passive"))
      (node (ref "U$1") (pin "P$9") (pinfunction "SCL_P$9") (pintype "bidirectional"))
      (node (ref "U$3") (pin "7") (pinfunction "SCL_7") (pintype "bidirectional"))
      (node (ref "U1") (pin "28") (pinfunction "PC5(ADC5/SCL)_28") (pintype "bidirectional"))
    )
    (net (code "61") (name "SDA") (class "Default")
      (node (ref "R3") (pin "1") (pinfunction "1_1") (pintype "passive"))
      (node (ref "SV1") (pin "4") (pinfunction "4_4") (pintype "passive"))
      (node (ref "U$1") (pin "P$10") (pinfunction "SDAI_P$10") (pintype "bidirectional"))
      (node (ref "U$1") (pin "P$11") (pinfunction "SDAO_P$11") (pintype "bidirectional"))
      (node (ref "U$3") (pin "8") (pinfunction "SDA_8") (pintype "bidirectional"))
      (node (ref "U1") (pin "27") (pinfunction "PC4(ADC4/SDA)_27") (pintype "bidirectional"))
    )
    (net (code "62") (name "TX") (class "Default")
      (node (ref "BR1") (pin "6") (pinfunction "UTX_6") (pintype "bidirectional"))
      (node (ref "SV1") (pin "5") (pinfunction "5_5") (pintype "passive"))
      (node (ref "U1") (pin "2") (pinfunction "PD0(RXD)_2") (pintype "bidirectional"))
    )
    (net (code "63") (name "V+") (class "Default")
      (node (ref "R11") (pin "2") (pinfunction "2_2") (pintype "passive"))
      (node (ref "U$1") (pin "P$1") (pinfunction "SENSE1-_P$1") (pintype "bidirectional"))
      (node (ref "X1") (pin "P$2") (pinfunction "P$2_P$2") (pintype "bidirectional"))
    )
    (net (code "64") (name "V-") (class "Default")
      (node (ref "R12") (pin "1") (pinfunction "1_1") (pintype "passive"))
      (node (ref "U$1") (pin "P$15") (pinfunction "SENS2+_P$15") (pintype "bidirectional"))
      (node (ref "X1") (pin "P$3") (pinfunction "P$3_P$3") (pintype "bidirectional"))
    )
    (net (code "65") (name "VIN") (class "Default")
      (node (ref "R11") (pin "1") (pinfunction "1_1") (pintype "passive"))
      (node (ref "U$1") (pin "P$2") (pinfunction "SENSE1+_P$2") (pintype "bidirectional"))
      (node (ref "X1") (pin "P$1") (pinfunction "P$1_P$1") (pintype "bidirectional"))
    )
    (net (code "66") (name "VLOAD") (class "Default")
      (node (ref "R12") (pin "2") (pinfunction "2_2") (pintype "passive"))
      (node (ref "U$1") (pin "P$16") (pinfunction "SENSE2-_P$16") (pintype "bidirectional"))
      (node (ref "U$4") (pin "D") (pinfunction "D_D") (pintype "bidirectional"))
      (node (ref "U$5") (pin "D") (pinfunction "D_D") (pintype "bidirectional"))
    )
    (net (code "67") (name "V_USB") (class "Default")
      (node (ref "D6") (pin "A") (pinfunction "A_A") (pintype "passive"))
      (node (ref "J1") (pin "VBUS") (pinfunction "VBUS_VBUS") (pintype "power_in"))
    )
    (net (code "68") (name "unconnected-(BR1-GP2-Pad7)") (class "Default")
      (node (ref "BR1") (pin "7") (pinfunction "GP2_7") (pintype "bidirectional"))
    )
    (net (code "69") (name "unconnected-(BR1-GP3-Pad8)") (class "Default")
      (node (ref "BR1") (pin "8") (pinfunction "GP3_8") (pintype "bidirectional"))
    )
    (net (code "70") (name "unconnected-(BR1-RESET-Pad4)") (class "Default")
      (node (ref "BR1") (pin "4") (pinfunction "RESET_4") (pintype "bidirectional"))
    )
    (net (code "71") (name "unconnected-(BR1-SCL-Pad10)") (class "Default")
      (node (ref "BR1") (pin "10") (pinfunction "SCL_10") (pintype "bidirectional"))
    )
    (net (code "72") (name "unconnected-(BR1-SDA-Pad9)") (class "Default")
      (node (ref "BR1") (pin "9") (pinfunction "SDA_9") (pintype "bidirectional"))
    )
    (net (code "73") (name "unconnected-(J1-PadID)") (class "Default")
      (node (ref "J1") (pin "ID") (pinfunction "ID_ID") (pintype "bidirectional"))
    )
    (net (code "74") (name "unconnected-(J2-NC-Pad3)") (class "Default")
      (node (ref "J2") (pin "3") (pinfunction "NC_3") (pintype "no_connect"))
    )
    (net (code "75") (name "unconnected-(LCD1-DB0-Pad7)") (class "Default")
      (node (ref "LCD1") (pin "7") (pinfunction "DB0_7") (pintype "bidirectional"))
    )
    (net (code "76") (name "unconnected-(LCD1-DB1-Pad8)") (class "Default")
      (node (ref "LCD1") (pin "8") (pinfunction "DB1_8") (pintype "bidirectional"))
    )
    (net (code "77") (name "unconnected-(LCD1-DB2-Pad9)") (class "Default")
      (node (ref "LCD1") (pin "9") (pinfunction "DB2_9") (pintype "bidirectional"))
    )
    (net (code "78") (name "unconnected-(LCD1-DB3-Pad10)") (class "Default")
      (node (ref "LCD1") (pin "10") (pinfunction "DB3_10") (pintype "bidirectional"))
    )
    (net (code "79") (name "unconnected-(U$1-GPIO3-PadP$4)") (class "Default")
      (node (ref "U$1") (pin "P$4") (pinfunction "GPIO3_P$4") (pintype "bidirectional"))
    )
    (net (code "80") (name "unconnected-(U$3-LAT0-Pad6)") (class "Default")
      (node (ref "U$3") (pin "6") (pinfunction "LAT0_6") (pintype "bidirectional"))
    )
    (net (code "81") (name "unconnected-(U$3-NC-Pad4)") (class "Default")
      (node (ref "U$3") (pin "4") (pinfunction "NC_4") (pintype "bidirectional"))
    )
    (net (code "82") (name "unconnected-(U$3-VFRE0-Pad2)") (class "Default")
      (node (ref "U$3") (pin "2") (pinfunction "VFRE0_2") (pintype "bidirectional"))
    )
  )
)
